# SoftCore_SA_P2_PG3.net
KiCad netlist of a schematic drawn in Altium Designer
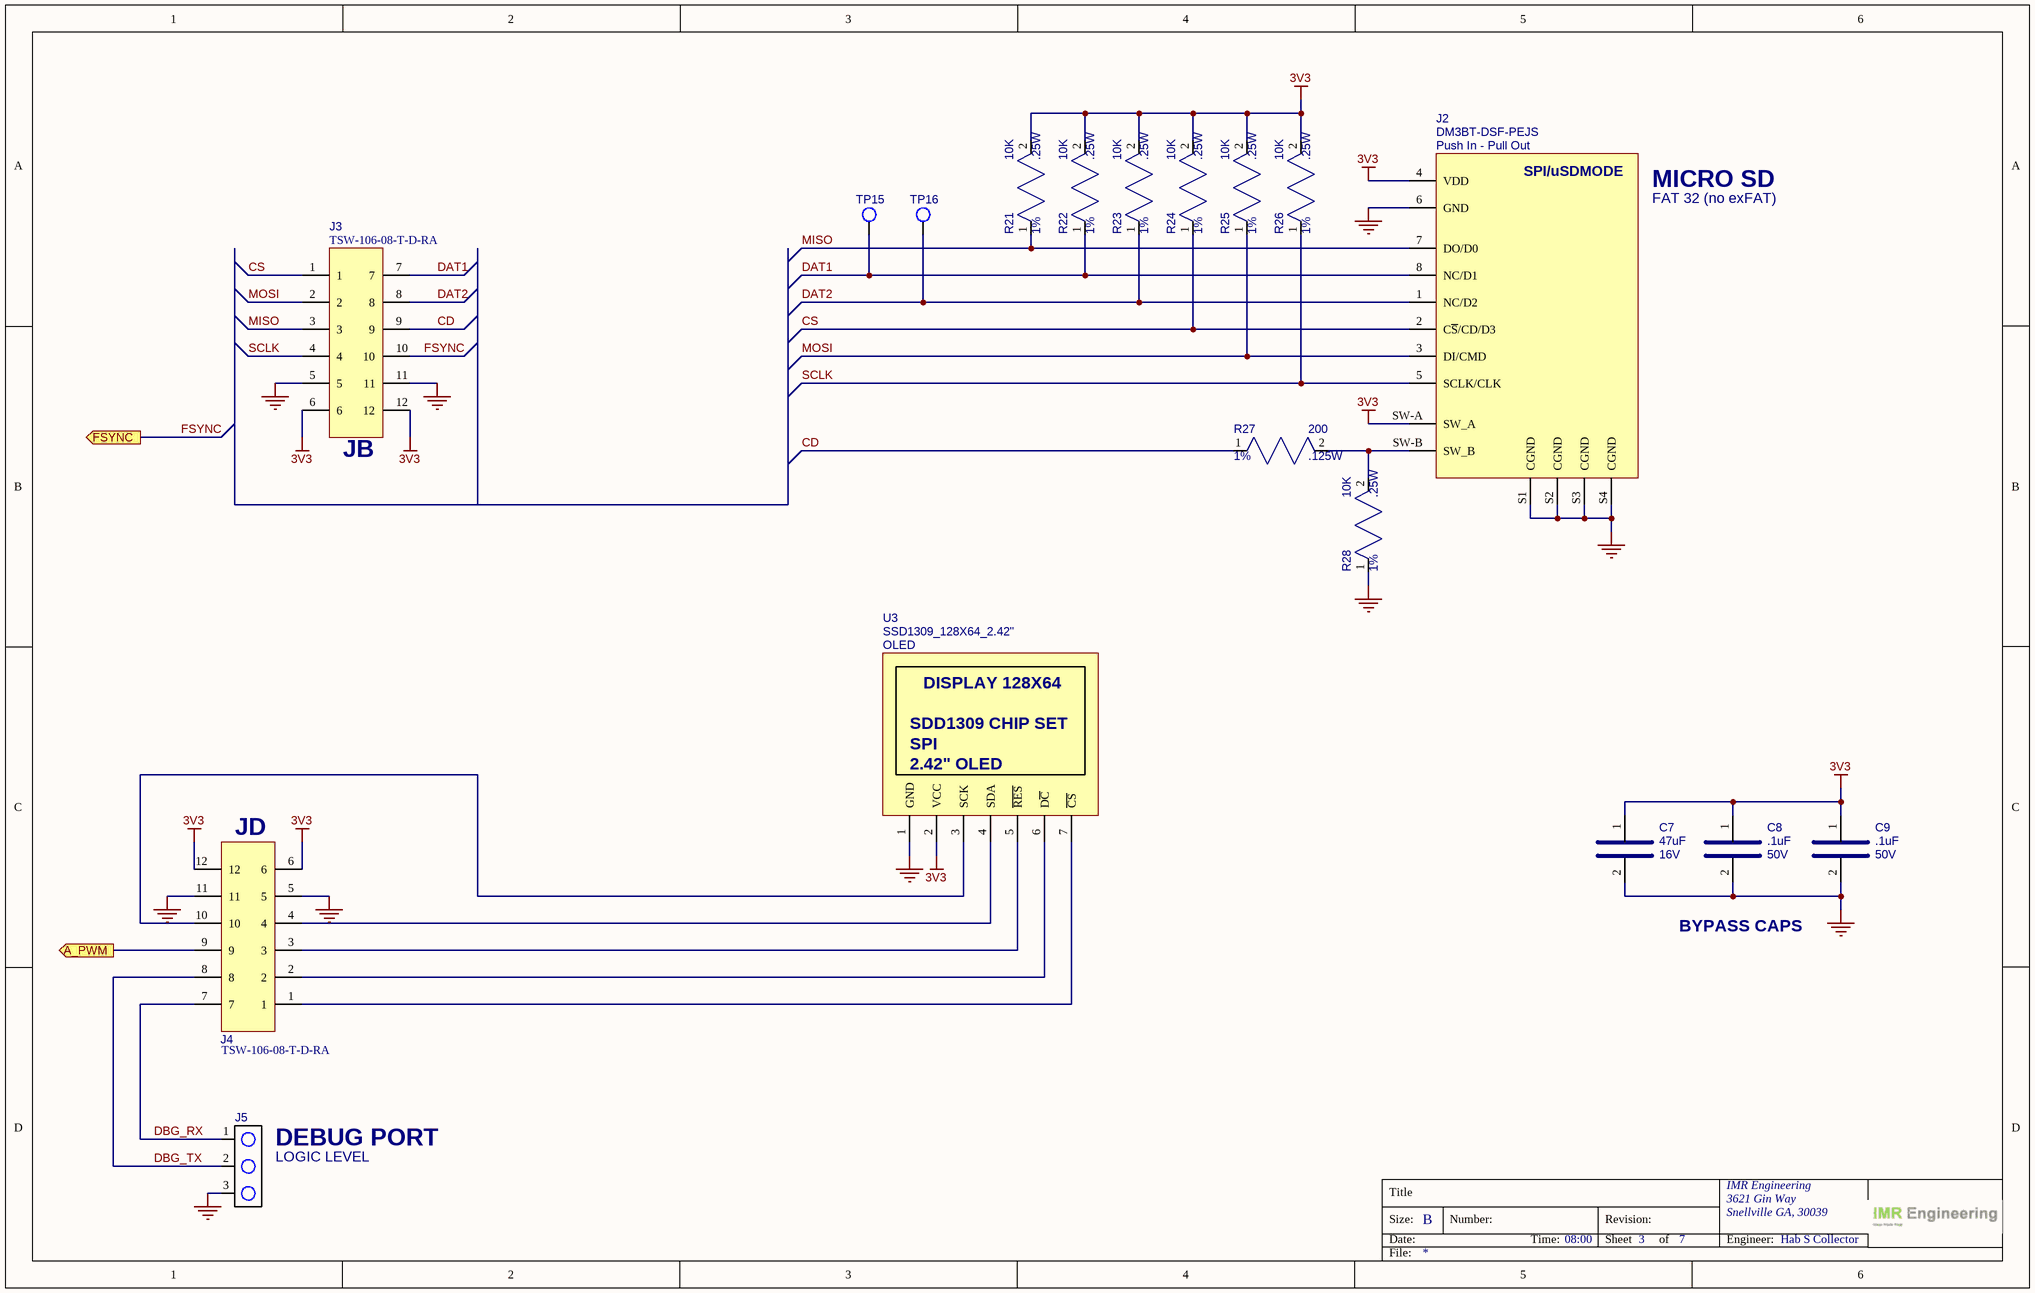
[diagram p0: SoftCore_SA_P2_PG3.SchDoc]

(export (version "E")
  (design (tool "Eeschema 10.0.6"))
  (components
    (comp (ref "C7")
      (value "47uF")
      (footprint "CAP_1210")
      (description "CAP CER 47UF 50V X5R 1210")
      (fields
        (field (name "MFG") "Murata Electronics")
        (field (name "VOLTAGE") "16V")
        (field (name "Comment") "GRM32ER60J476ME20L")
      )
      (libsource (lib "IMR_LIB_SCH_R2") (part "CAP_SMD_47UF_16V_1210"))
    )
    (comp (ref "C8")
      (value ".1uF")
      (footprint "CAP_0805")
      (description "CAP CER 0.1UF 50V X7R 0805")
      (fields
        (field (name "MFG") "KYOCERA AVX")
        (field (name "VOLTAGE") "50V")
        (field (name "Comment") "KGM21NR71H104KT")
      )
      (libsource (lib "IMR_LIB_SCH_R2") (part "CAP_SMD_0.1UF_50V_0805"))
    )
    (comp (ref "C9")
      (value ".1uF")
      (footprint "CAP_0805")
      (description "CAP CER 0.1UF 50V X7R 0805")
      (fields
        (field (name "MFG") "KYOCERA AVX")
        (field (name "VOLTAGE") "50V")
        (field (name "Comment") "KGM21NR71H104KT")
      )
      (libsource (lib "IMR_LIB_SCH_R2") (part "CAP_SMD_0.1UF_50V_0805"))
    )
    (comp (ref "J2")
      (value "Push In - Pull Out")
      (footprint "HRS_DM3BT-DSF-PEJS")
      (description "CONN MICRO SD CARD R/A SMD")
      (fields
        (field (name "MFG") "Hirose Electric Co Ltd")
        (field (name "MFG_PN") "DM3BT-DSF-PEJS")
        (field (name "Comment") "DM3BT-DSF-PEJS")
      )
      (libsource (lib "IMR_LIB_SCH_R2") (part "CONN_MICRO-SD_DM3BT-DSF-PEJS"))
    )
    (comp (ref "J3")
      (value "TSW-106-08-T-D-RA")
      (footprint "SAMTEC_TSW-106-08-T-D-RA")
      (description "CONN HEADER R/A 12POS 2.54MM")
      (fields (field (name "MFG") "Samtec Inc.") (field (name "MFG_PN") "TSW-106-08-T-D-RA"))
      (libsource (lib "") (part "CONN_HEADER_12P_100MIL_RA_1"))
    )
    (comp (ref "J4")
      (value "TSW-106-08-T-D-RA")
      (footprint "SAMTEC_TSW-106-08-T-D-RA")
      (description "CONN HEADER R/A 12POS 2.54MM")
      (fields (field (name "MFG") "Samtec Inc.") (field (name "MFG_PN") "TSW-106-08-T-D-RA"))
      (libsource (lib "IMR_LIB_SCH_R2") (part "CONN_HEADER_12P_100MIL_RA"))
    )
    (comp (ref "J5")
      (value "PREC003SFAN-RC")
      (footprint "HDR_1X3_100MILL")
      (description "CONN HEADER VERT 3POS 2.54MM")
      (fields (field (name "MFG") "Sullins Connector Solutions"))
      (libsource (lib "IMR_LIB_SCH_R2") (part "CONN_HEADER_3P_100MIL_VERT"))
    )
    (comp (ref "R21")
      (value "10K")
      (footprint "RES_0805")
      (description "RES SMD 10K OHM 1% 1/4W 0805")
      (fields
        (field (name "MFG") "Yageo")
        (field (name "POWER") ".25W")
        (field (name "TOLERANCE") "1%")
        (field (name "Comment") "RC0805FR-7W10KL")
      )
      (libsource (lib "IMR_LIB_SCH_R2") (part "RES_SMD_10K_0805_1/4W_1%"))
    )
    (comp (ref "R22")
      (value "10K")
      (footprint "RES_0805")
      (description "RES SMD 10K OHM 1% 1/4W 0805")
      (fields
        (field (name "MFG") "Yageo")
        (field (name "POWER") ".25W")
        (field (name "TOLERANCE") "1%")
        (field (name "Comment") "RC0805FR-7W10KL")
      )
      (libsource (lib "IMR_LIB_SCH_R2") (part "RES_SMD_10K_0805_1/4W_1%"))
    )
    (comp (ref "R23")
      (value "10K")
      (footprint "RES_0805")
      (description "RES SMD 10K OHM 1% 1/4W 0805")
      (fields
        (field (name "MFG") "Yageo")
        (field (name "POWER") ".25W")
        (field (name "TOLERANCE") "1%")
        (field (name "Comment") "RC0805FR-7W10KL")
      )
      (libsource (lib "IMR_LIB_SCH_R2") (part "RES_SMD_10K_0805_1/4W_1%"))
    )
    (comp (ref "R24")
      (value "10K")
      (footprint "RES_0805")
      (description "RES SMD 10K OHM 1% 1/4W 0805")
      (fields
        (field (name "MFG") "Yageo")
        (field (name "POWER") ".25W")
        (field (name "TOLERANCE") "1%")
        (field (name "Comment") "RC0805FR-7W10KL")
      )
      (libsource (lib "IMR_LIB_SCH_R2") (part "RES_SMD_10K_0805_1/4W_1%"))
    )
    (comp (ref "R25")
      (value "10K")
      (footprint "RES_0805")
      (description "RES SMD 10K OHM 1% 1/4W 0805")
      (fields
        (field (name "MFG") "Yageo")
        (field (name "POWER") ".25W")
        (field (name "TOLERANCE") "1%")
        (field (name "Comment") "RC0805FR-7W10KL")
      )
      (libsource (lib "IMR_LIB_SCH_R2") (part "RES_SMD_10K_0805_1/4W_1%"))
    )
    (comp (ref "R26")
      (value "10K")
      (footprint "RES_0805")
      (description "RES SMD 10K OHM 1% 1/4W 0805")
      (fields
        (field (name "MFG") "Yageo")
        (field (name "POWER") ".25W")
        (field (name "TOLERANCE") "1%")
        (field (name "Comment") "RC0805FR-7W10KL")
      )
      (libsource (lib "IMR_LIB_SCH_R2") (part "RES_SMD_10K_0805_1/4W_1%"))
    )
    (comp (ref "R27")
      (value "200")
      (footprint "RES_0805")
      (description "RES SMD 200 OHM 1% 1/8W 0805")
      (fields
        (field (name "MFG") "Yageo")
        (field (name "POWER") ".125W")
        (field (name "TOLERANCE") "1%")
        (field (name "Comment") "RC0805FR-07200RL")
      )
      (libsource (lib "IMR_LIB_SCH_R2") (part "RES_SMD_200_0805_1/8W_1%"))
    )
    (comp (ref "R28")
      (value "10K")
      (footprint "RES_0805")
      (description "RES SMD 10K OHM 1% 1/4W 0805")
      (fields
        (field (name "MFG") "Yageo")
        (field (name "POWER") ".25W")
        (field (name "TOLERANCE") "1%")
        (field (name "Comment") "RC0805FR-7W10KL")
      )
      (libsource (lib "IMR_LIB_SCH_R2") (part "RES_SMD_10K_0805_1/4W_1%"))
    )
    (comp (ref "TP15")
      (value "~")
      (footprint "TEST_POINT_35MIL_TH")
      (description "TEST POINT TH FITS DSO PROBE TIP")
      (libsource (lib "IMR_LIB_SCH_R2") (part "CONN_TEST_POINT_TH_PROBE_TIP"))
    )
    (comp (ref "TP16")
      (value "~")
      (footprint "TEST_POINT_35MIL_TH")
      (description "TEST POINT TH FITS DSO PROBE TIP")
      (libsource (lib "IMR_LIB_SCH_R2") (part "CONN_TEST_POINT_TH_PROBE_TIP"))
    )
    (comp (ref "U3")
      (value "SSD1309_128X64_2.42\"")
      (footprint "MODULE_DISPLAY_128X64_2.42")
      (description "DISPLAY 128X64 SSD1309 2.42\" OLED WHITE")
      (fields
        (field (name "MFG") "UNKNOWN")
        (field (name "TYPE") "OLED")
        (field (name "MFG_PN") "SSD1309_128X64_2.42\"")
      )
      (libsource (lib "IMR_LIB_SCH_R2") (part "MODULE_DISPLAY_128X64_2.42"))
    )
  )
  (nets
    (net (code "1") (name "/A_PWM") (class "Default")
      (node (ref "J4") (pin "9") (pinfunction "9_9") (pintype "passive"))
    )
    (net (code "2") (name "/CD") (class "Default")
      (node (ref "J3") (pin "9") (pinfunction "9_9") (pintype "passive"))
      (node (ref "R27") (pin "1") (pinfunction "1_1") (pintype "passive"))
    )
    (net (code "3") (name "/CS") (class "Default")
      (node (ref "J2") (pin "2") (pinfunction "C~{S}/CD/D3_2") (pintype "passive"))
      (node (ref "J3") (pin "1") (pinfunction "1_1") (pintype "passive"))
      (node (ref "R24") (pin "1") (pinfunction "1_1") (pintype "passive"))
    )
    (net (code "4") (name "/DAT1") (class "Default")
      (node (ref "J2") (pin "8") (pinfunction "NC/D1_8") (pintype "passive"))
      (node (ref "J3") (pin "7") (pinfunction "7_7") (pintype "passive"))
      (node (ref "R22") (pin "1") (pinfunction "1_1") (pintype "passive"))
      (node (ref "TP15") (pin "1") (pintype "passive"))
    )
    (net (code "5") (name "/DAT2") (class "Default")
      (node (ref "J2") (pin "1") (pinfunction "NC/D2_1") (pintype "passive"))
      (node (ref "J3") (pin "8") (pinfunction "8_8") (pintype "passive"))
      (node (ref "R23") (pin "1") (pinfunction "1_1") (pintype "passive"))
      (node (ref "TP16") (pin "1") (pintype "passive"))
    )
    (net (code "6") (name "/DBG_RX") (class "Default")
      (node (ref "J4") (pin "7") (pinfunction "7_7") (pintype "passive"))
      (node (ref "J5") (pin "1") (pintype "passive"))
    )
    (net (code "7") (name "/DBG_TX") (class "Default")
      (node (ref "J4") (pin "8") (pinfunction "8_8") (pintype "passive"))
      (node (ref "J5") (pin "2") (pintype "passive"))
    )
    (net (code "8") (name "/FSYNC") (class "Default")
      (node (ref "J3") (pin "10") (pinfunction "10_10") (pintype "passive"))
    )
    (net (code "9") (name "/MISO") (class "Default")
      (node (ref "J2") (pin "7") (pinfunction "DO/D0_7") (pintype "passive"))
      (node (ref "J3") (pin "3") (pinfunction "3_3") (pintype "passive"))
      (node (ref "R21") (pin "1") (pinfunction "1_1") (pintype "passive"))
    )
    (net (code "10") (name "/MOSI") (class "Default")
      (node (ref "J2") (pin "3") (pinfunction "DI/CMD_3") (pintype "passive"))
      (node (ref "J3") (pin "2") (pinfunction "2_2") (pintype "passive"))
      (node (ref "R25") (pin "1") (pinfunction "1_1") (pintype "passive"))
    )
    (net (code "11") (name "/SCLK") (class "Default")
      (node (ref "J2") (pin "5") (pinfunction "SCLK/CLK_5") (pintype "passive"))
      (node (ref "J3") (pin "4") (pinfunction "4_4") (pintype "passive"))
      (node (ref "R26") (pin "1") (pinfunction "1_1") (pintype "passive"))
    )
    (net (code "12") (name "3V3") (class "Default")
      (node (ref "C7") (pin "1") (pinfunction "1_1") (pintype "passive"))
      (node (ref "C8") (pin "1") (pinfunction "1_1") (pintype "passive"))
      (node (ref "C9") (pin "1") (pinfunction "1_1") (pintype "passive"))
      (node (ref "J2") (pin "4") (pinfunction "VDD_4") (pintype "passive"))
      (node (ref "J2") (pin "SW-A") (pinfunction "SW_A_SW-A") (pintype "passive"))
      (node (ref "J3") (pin "12") (pinfunction "12_12") (pintype "passive"))
      (node (ref "J3") (pin "6") (pinfunction "6_6") (pintype "passive"))
      (node (ref "J4") (pin "12") (pinfunction "12_12") (pintype "passive"))
      (node (ref "J4") (pin "6") (pinfunction "6_6") (pintype "passive"))
      (node (ref "R21") (pin "2") (pinfunction "2_2") (pintype "passive"))
      (node (ref "R22") (pin "2") (pinfunction "2_2") (pintype "passive"))
      (node (ref "R23") (pin "2") (pinfunction "2_2") (pintype "passive"))
      (node (ref "R24") (pin "2") (pinfunction "2_2") (pintype "passive"))
      (node (ref "R25") (pin "2") (pinfunction "2_2") (pintype "passive"))
      (node (ref "R26") (pin "2") (pinfunction "2_2") (pintype "passive"))
      (node (ref "U3") (pin "2") (pinfunction "VCC_2") (pintype "passive"))
    )
    (net (code "13") (name "GND") (class "Default")
      (node (ref "C7") (pin "2") (pinfunction "2_2") (pintype "passive"))
      (node (ref "C8") (pin "2") (pinfunction "2_2") (pintype "passive"))
      (node (ref "C9") (pin "2") (pinfunction "2_2") (pintype "passive"))
      (node (ref "J2") (pin "6") (pinfunction "GND_6") (pintype "passive"))
      (node (ref "J2") (pin "S1") (pinfunction "CGND_S1") (pintype "passive"))
      (node (ref "J2") (pin "S2") (pinfunction "CGND_S2") (pintype "passive"))
      (node (ref "J2") (pin "S3") (pinfunction "CGND_S3") (pintype "passive"))
      (node (ref "J2") (pin "S4") (pinfunction "CGND_S4") (pintype "passive"))
      (node (ref "J3") (pin "11") (pinfunction "11_11") (pintype "passive"))
      (node (ref "J3") (pin "5") (pinfunction "5_5") (pintype "passive"))
      (node (ref "J4") (pin "11") (pinfunction "11_11") (pintype "passive"))
      (node (ref "J4") (pin "5") (pinfunction "5_5") (pintype "passive"))
      (node (ref "J5") (pin "3") (pintype "passive"))
      (node (ref "R28") (pin "1") (pinfunction "1_1") (pintype "passive"))
      (node (ref "U3") (pin "1") (pinfunction "GND_1") (pintype "passive"))
    )
    (net (code "14") (name "Net-(J2-SW_B)") (class "Default")
      (node (ref "J2") (pin "SW-B") (pinfunction "SW_B_SW-B") (pintype "passive"))
      (node (ref "R27") (pin "2") (pinfunction "2_2") (pintype "passive"))
      (node (ref "R28") (pin "2") (pinfunction "2_2") (pintype "passive"))
    )
    (net (code "15") (name "Net-(U3-D~{C})") (class "Default")
      (node (ref "J4") (pin "2") (pinfunction "2_2") (pintype "passive"))
      (node (ref "U3") (pin "6") (pinfunction "D~{C}_6") (pintype "passive"))
    )
    (net (code "16") (name "Net-(U3-SCK)") (class "Default")
      (node (ref "J4") (pin "10") (pinfunction "10_10") (pintype "passive"))
      (node (ref "U3") (pin "3") (pinfunction "SCK_3") (pintype "passive"))
    )
    (net (code "17") (name "Net-(U3-SDA)") (class "Default")
      (node (ref "J4") (pin "4") (pinfunction "4_4") (pintype "passive"))
      (node (ref "U3") (pin "4") (pinfunction "SDA_4") (pintype "passive"))
    )
    (net (code "18") (name "Net-(U3-~{CS})") (class "Default")
      (node (ref "J4") (pin "1") (pinfunction "1_1") (pintype "passive"))
      (node (ref "U3") (pin "7") (pinfunction "~{CS}_7") (pintype "passive"))
    )
    (net (code "19") (name "Net-(U3-~{RES})") (class "Default")
      (node (ref "J4") (pin "3") (pinfunction "3_3") (pintype "passive"))
      (node (ref "U3") (pin "5") (pinfunction "~{RES}_5") (pintype "passive"))
    )
  )
)
